# 8_IR.net
KiCad netlist of a schematic drawn in Altium Designer
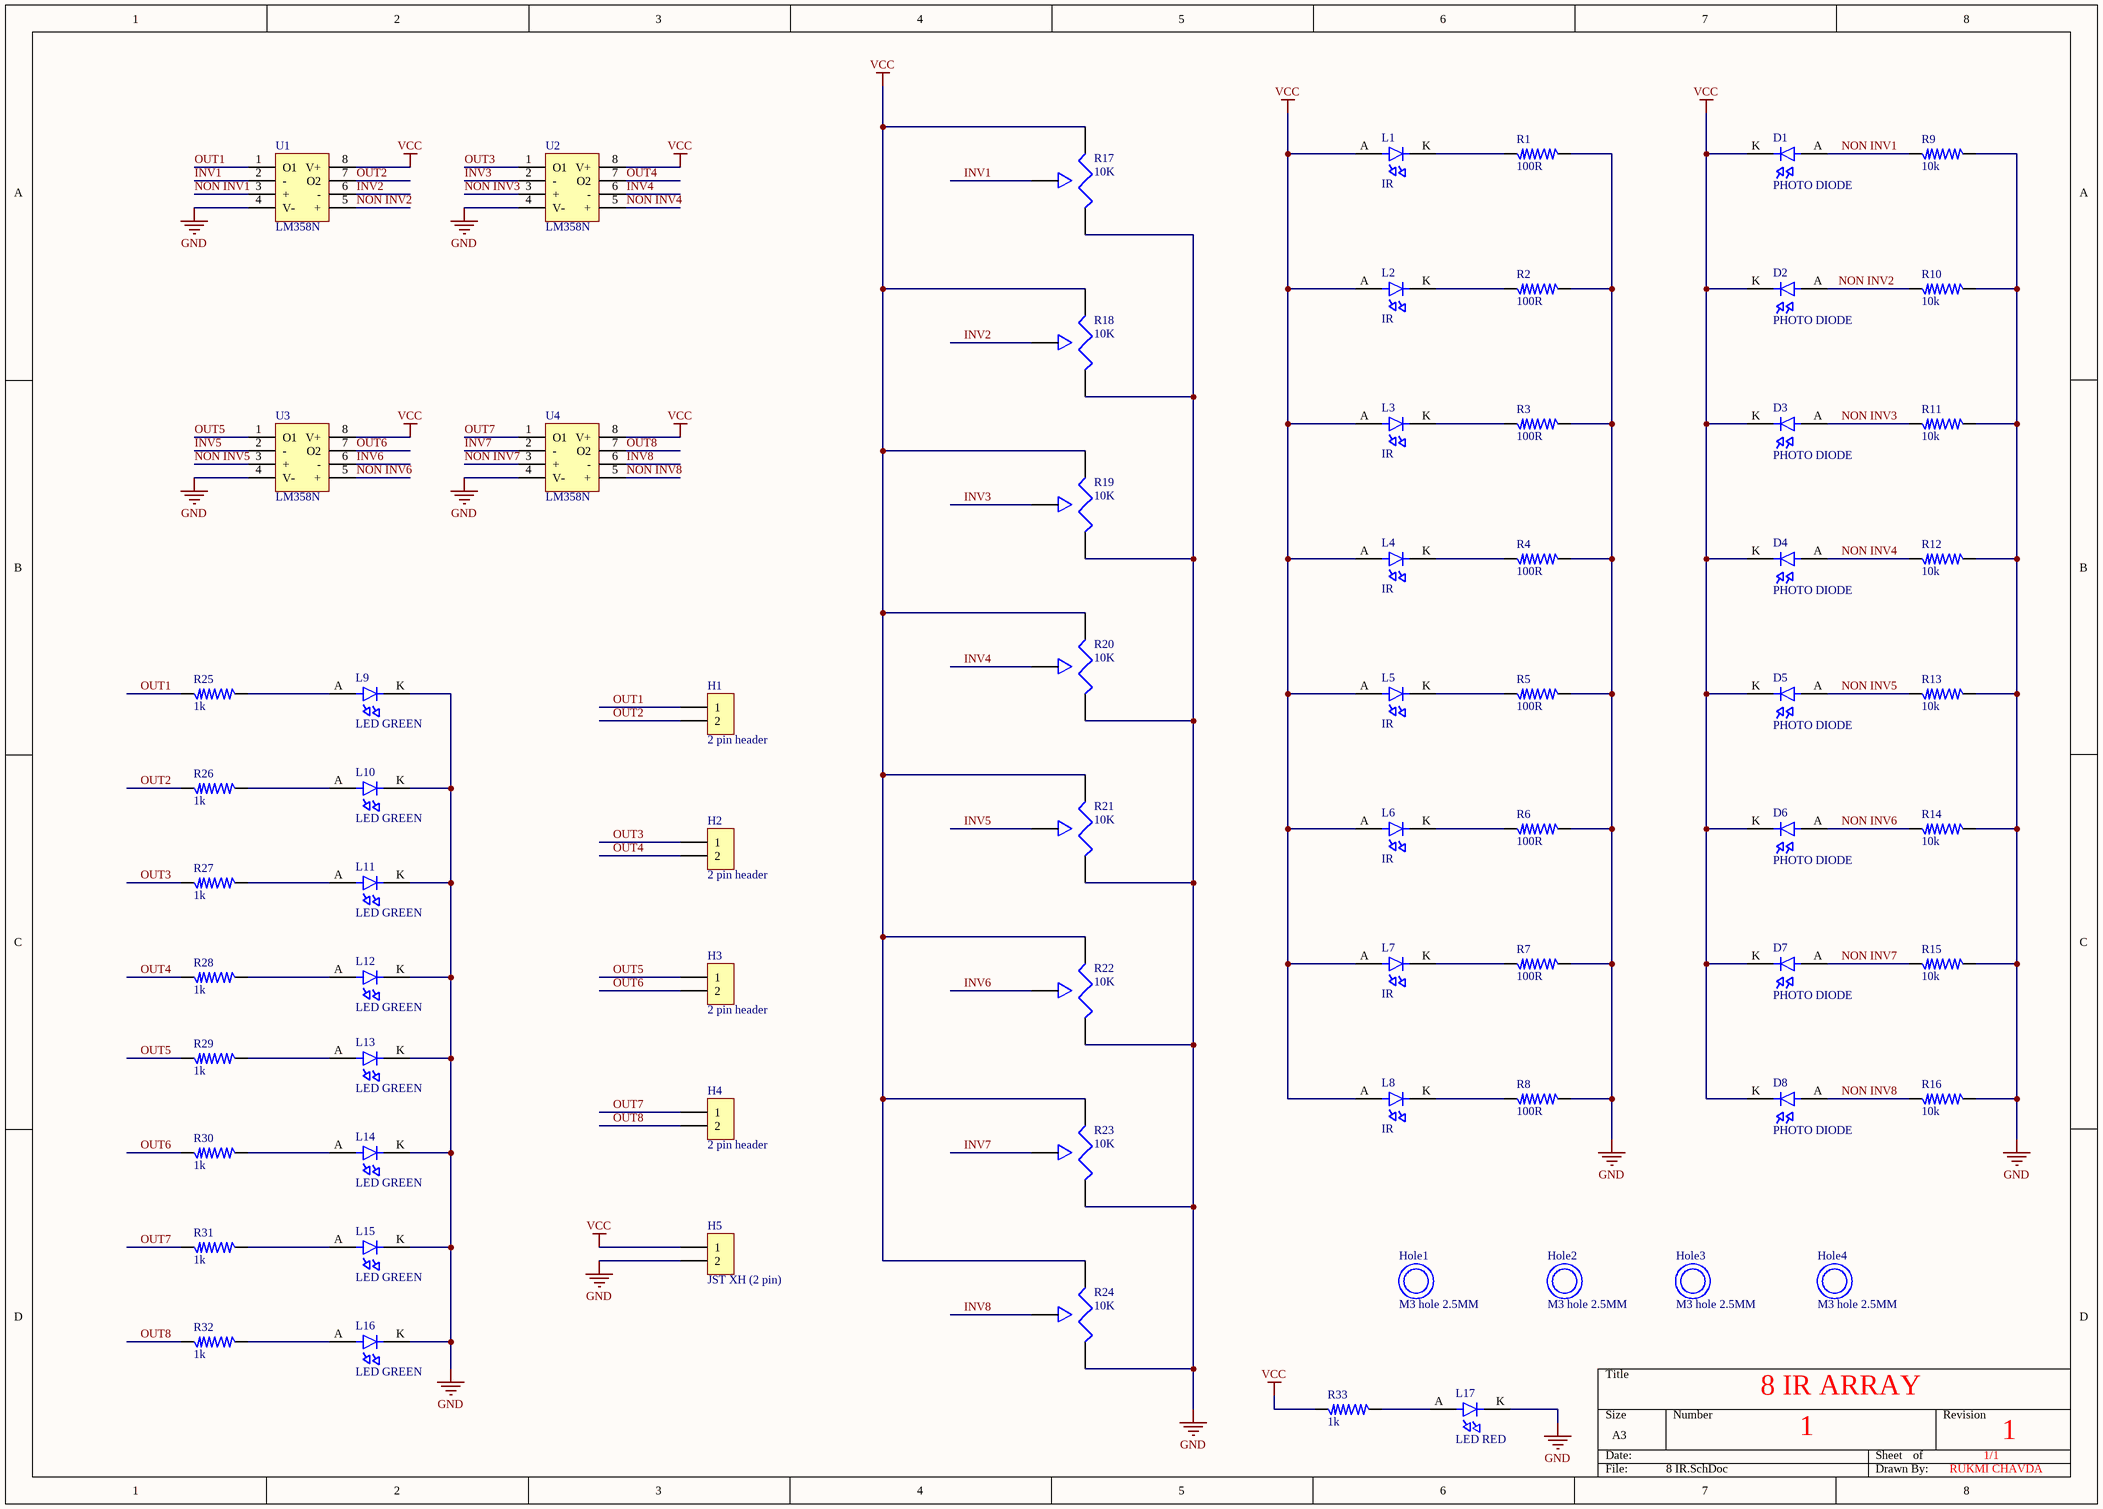
[diagram p0: 8 IR.SchDoc]

(export (version "E")
  (design (tool "Eeschema 10.0.6"))
  (components
    (comp (ref "D1")
      (value "PHOTO DIODE")
      (footprint "PHOYODIODE")
      (description "VISHAY         BPW24R             PHOTODIODE, 11PF")
      (libsource (lib "LEDs") (part "PHOTO DIODE"))
    )
    (comp (ref "D2")
      (value "PHOTO DIODE")
      (footprint "PHOYODIODE")
      (description "VISHAY         BPW24R             PHOTODIODE, 11PF")
      (libsource (lib "LEDs") (part "PHOTO DIODE"))
    )
    (comp (ref "D3")
      (value "PHOTO DIODE")
      (footprint "PHOYODIODE")
      (description "VISHAY         BPW24R             PHOTODIODE, 11PF")
      (libsource (lib "LEDs") (part "PHOTO DIODE"))
    )
    (comp (ref "D4")
      (value "PHOTO DIODE")
      (footprint "PHOYODIODE")
      (description "VISHAY         BPW24R             PHOTODIODE, 11PF")
      (libsource (lib "LEDs") (part "PHOTO DIODE"))
    )
    (comp (ref "D5")
      (value "PHOTO DIODE")
      (footprint "PHOYODIODE")
      (description "VISHAY         BPW24R             PHOTODIODE, 11PF")
      (libsource (lib "LEDs") (part "PHOTO DIODE"))
    )
    (comp (ref "D6")
      (value "PHOTO DIODE")
      (footprint "PHOYODIODE")
      (description "VISHAY         BPW24R             PHOTODIODE, 11PF")
      (libsource (lib "LEDs") (part "PHOTO DIODE"))
    )
    (comp (ref "D7")
      (value "PHOTO DIODE")
      (footprint "PHOYODIODE")
      (description "VISHAY         BPW24R             PHOTODIODE, 11PF")
      (libsource (lib "LEDs") (part "PHOTO DIODE"))
    )
    (comp (ref "D8")
      (value "PHOTO DIODE")
      (footprint "PHOYODIODE")
      (description "VISHAY         BPW24R             PHOTODIODE, 11PF")
      (libsource (lib "LEDs") (part "PHOTO DIODE"))
    )
    (comp (ref "H1")
      (value "2 pin header")
      (footprint "header 2")
      (description "connector")
      (libsource (lib "CONNECTORS AND HEADERS") (part "2 pin header"))
    )
    (comp (ref "H2")
      (value "2 pin header")
      (footprint "header 2")
      (description "connector")
      (libsource (lib "CONNECTORS AND HEADERS") (part "2 pin header"))
    )
    (comp (ref "H3")
      (value "2 pin header")
      (footprint "header 2")
      (description "connector")
      (libsource (lib "CONNECTORS AND HEADERS") (part "2 pin header"))
    )
    (comp (ref "H4")
      (value "2 pin header")
      (footprint "header 2")
      (description "connector")
      (libsource (lib "CONNECTORS AND HEADERS") (part "2 pin header"))
    )
    (comp (ref "H5")
      (value "JST XH (2 pin)")
      (footprint "jst 2 pin XH")
      (description "Conn Shrouded Header (4 Sides) HDR 2 POS 2.5mm Solder ST Thru-Hole Box")
      (fields
        (field (name "MANUFACTURER") "JST")
        (field (name "MANUFACTURER PART NUMBER") "B2B-XH-A(LF)(SN)")
      )
      (libsource (lib "CONNECTORS AND HEADERS") (part "JST XH (2 pin)"))
    )
    (comp (ref "Hole1")
      (value "M3 hole 2.5MM")
      (footprint "M3 Hole")
      (description "Mounting hole")
      (libsource (lib "Pades and Mounting holes") (part "M3 hole 2.5MM"))
    )
    (comp (ref "Hole2")
      (value "M3 hole 2.5MM")
      (footprint "M3 Hole")
      (description "Mounting hole")
      (libsource (lib "Pades and Mounting holes") (part "M3 hole 2.5MM"))
    )
    (comp (ref "Hole3")
      (value "M3 hole 2.5MM")
      (footprint "M3 Hole")
      (description "Mounting hole")
      (libsource (lib "Pades and Mounting holes") (part "M3 hole 2.5MM"))
    )
    (comp (ref "Hole4")
      (value "M3 hole 2.5MM")
      (footprint "M3 Hole")
      (description "Mounting hole")
      (libsource (lib "Pades and Mounting holes") (part "M3 hole 2.5MM"))
    )
    (comp (ref "L1")
      (value "IR")
      (footprint "LED IR")
      (description "EMITTER IR 940NM 100MA RADIAL")
      (libsource (lib "LEDs") (part "IR"))
    )
    (comp (ref "L2")
      (value "IR")
      (footprint "LED IR")
      (description "EMITTER IR 940NM 100MA RADIAL")
      (libsource (lib "LEDs") (part "IR"))
    )
    (comp (ref "L3")
      (value "IR")
      (footprint "LED IR")
      (description "EMITTER IR 940NM 100MA RADIAL")
      (libsource (lib "LEDs") (part "IR"))
    )
    (comp (ref "L4")
      (value "IR")
      (footprint "LED IR")
      (description "EMITTER IR 940NM 100MA RADIAL")
      (libsource (lib "LEDs") (part "IR"))
    )
    (comp (ref "L5")
      (value "IR")
      (footprint "LED IR")
      (description "EMITTER IR 940NM 100MA RADIAL")
      (libsource (lib "LEDs") (part "IR"))
    )
    (comp (ref "L6")
      (value "IR")
      (footprint "LED IR")
      (description "EMITTER IR 940NM 100MA RADIAL")
      (libsource (lib "LEDs") (part "IR"))
    )
    (comp (ref "L7")
      (value "IR")
      (footprint "LED IR")
      (description "EMITTER IR 940NM 100MA RADIAL")
      (libsource (lib "LEDs") (part "IR"))
    )
    (comp (ref "L8")
      (value "IR")
      (footprint "LED IR")
      (description "EMITTER IR 940NM 100MA RADIAL")
      (libsource (lib "LEDs") (part "IR"))
    )
    (comp (ref "L9")
      (value "LED GREEN")
      (footprint "LED GREEN")
      (description "LED GREEN DIFFUSED T-1 3/4 T/H")
      (libsource (lib "LEDs") (part "LED GREEN"))
    )
    (comp (ref "L10")
      (value "LED GREEN")
      (footprint "LED GREEN")
      (description "LED GREEN DIFFUSED T-1 3/4 T/H")
      (libsource (lib "LEDs") (part "LED GREEN"))
    )
    (comp (ref "L11")
      (value "LED GREEN")
      (footprint "LED GREEN")
      (description "LED GREEN DIFFUSED T-1 3/4 T/H")
      (libsource (lib "LEDs") (part "LED GREEN"))
    )
    (comp (ref "L12")
      (value "LED GREEN")
      (footprint "LED GREEN")
      (description "LED GREEN DIFFUSED T-1 3/4 T/H")
      (libsource (lib "LEDs") (part "LED GREEN"))
    )
    (comp (ref "L13")
      (value "LED GREEN")
      (footprint "LED GREEN")
      (description "LED GREEN DIFFUSED T-1 3/4 T/H")
      (libsource (lib "LEDs") (part "LED GREEN"))
    )
    (comp (ref "L14")
      (value "LED GREEN")
      (footprint "LED GREEN")
      (description "LED GREEN DIFFUSED T-1 3/4 T/H")
      (libsource (lib "LEDs") (part "LED GREEN"))
    )
    (comp (ref "L15")
      (value "LED GREEN")
      (footprint "LED GREEN")
      (description "LED GREEN DIFFUSED T-1 3/4 T/H")
      (libsource (lib "LEDs") (part "LED GREEN"))
    )
    (comp (ref "L16")
      (value "LED GREEN")
      (footprint "LED GREEN")
      (description "LED GREEN DIFFUSED T-1 3/4 T/H")
      (libsource (lib "LEDs") (part "LED GREEN"))
    )
    (comp (ref "L17")
      (value "LED RED")
      (footprint "LED RED")
      (description "LED RED CLEAR 5MM OVAL T/H")
      (libsource (lib "LEDs") (part "LED RED"))
    )
    (comp (ref "R1")
      (value "100R")
      (footprint "100R")
      (description "RES 100 OHM 1/4W 5% AXIAL")
      (fields (field (name "TOLERANCE") "5%"))
      (libsource (lib "Resistor") (part "100R"))
    )
    (comp (ref "R2")
      (value "100R")
      (footprint "100R")
      (description "RES 100 OHM 1/4W 5% AXIAL")
      (fields (field (name "TOLERANCE") "5%"))
      (libsource (lib "Resistor") (part "100R"))
    )
    (comp (ref "R3")
      (value "100R")
      (footprint "100R")
      (description "RES 100 OHM 1/4W 5% AXIAL")
      (fields (field (name "TOLERANCE") "5%"))
      (libsource (lib "Resistor") (part "100R"))
    )
    (comp (ref "R4")
      (value "100R")
      (footprint "100R")
      (description "RES 100 OHM 1/4W 5% AXIAL")
      (fields (field (name "TOLERANCE") "5%"))
      (libsource (lib "Resistor") (part "100R"))
    )
    (comp (ref "R5")
      (value "100R")
      (footprint "100R")
      (description "RES 100 OHM 1/4W 5% AXIAL")
      (fields (field (name "TOLERANCE") "5%"))
      (libsource (lib "Resistor") (part "100R"))
    )
    (comp (ref "R6")
      (value "100R")
      (footprint "100R")
      (description "RES 100 OHM 1/4W 5% AXIAL")
      (fields (field (name "TOLERANCE") "5%"))
      (libsource (lib "Resistor") (part "100R"))
    )
    (comp (ref "R7")
      (value "100R")
      (footprint "100R")
      (description "RES 100 OHM 1/4W 5% AXIAL")
      (fields (field (name "TOLERANCE") "5%"))
      (libsource (lib "Resistor") (part "100R"))
    )
    (comp (ref "R8")
      (value "100R")
      (footprint "100R")
      (description "RES 100 OHM 1/4W 5% AXIAL")
      (fields (field (name "TOLERANCE") "5%"))
      (libsource (lib "Resistor") (part "100R"))
    )
    (comp (ref "R9")
      (value "10k")
      (footprint "10k")
      (description "RES 10K OHM 1/4W 5% AXIAL")
      (fields (field (name "TOLERANCE") "5%"))
      (libsource (lib "Resistor") (part "10k"))
    )
    (comp (ref "R10")
      (value "10k")
      (footprint "10k")
      (description "RES 10K OHM 1/4W 5% AXIAL")
      (fields (field (name "TOLERANCE") "5%"))
      (libsource (lib "Resistor") (part "10k"))
    )
    (comp (ref "R11")
      (value "10k")
      (footprint "10k")
      (description "RES 10K OHM 1/4W 5% AXIAL")
      (fields (field (name "TOLERANCE") "5%"))
      (libsource (lib "Resistor") (part "10k"))
    )
    (comp (ref "R12")
      (value "10k")
      (footprint "10k")
      (description "RES 10K OHM 1/4W 5% AXIAL")
      (fields (field (name "TOLERANCE") "5%"))
      (libsource (lib "Resistor") (part "10k"))
    )
    (comp (ref "R13")
      (value "10k")
      (footprint "10k")
      (description "RES 10K OHM 1/4W 5% AXIAL")
      (fields (field (name "TOLERANCE") "5%"))
      (libsource (lib "Resistor") (part "10k"))
    )
    (comp (ref "R14")
      (value "10k")
      (footprint "10k")
      (description "RES 10K OHM 1/4W 5% AXIAL")
      (fields (field (name "TOLERANCE") "5%"))
      (libsource (lib "Resistor") (part "10k"))
    )
    (comp (ref "R15")
      (value "10k")
      (footprint "10k")
      (description "RES 10K OHM 1/4W 5% AXIAL")
      (fields (field (name "TOLERANCE") "5%"))
      (libsource (lib "Resistor") (part "10k"))
    )
    (comp (ref "R16")
      (value "10k")
      (footprint "10k")
      (description "RES 10K OHM 1/4W 5% AXIAL")
      (fields (field (name "TOLERANCE") "5%"))
      (libsource (lib "Resistor") (part "10k"))
    )
    (comp (ref "R17")
      (value "10K")
      (footprint "trimer pot")
      (description "Trimmer pot comman for all")
      (libsource (lib "Resistor") (part "potentiometer 1"))
    )
    (comp (ref "R18")
      (value "10K")
      (footprint "trimer pot")
      (description "Trimmer pot comman for all")
      (libsource (lib "Resistor") (part "potentiometer 1"))
    )
    (comp (ref "R19")
      (value "10K")
      (footprint "trimer pot")
      (description "Trimmer pot comman for all")
      (libsource (lib "Resistor") (part "potentiometer 1"))
    )
    (comp (ref "R20")
      (value "10K")
      (footprint "trimer pot")
      (description "Trimmer pot comman for all")
      (libsource (lib "Resistor") (part "potentiometer 1"))
    )
    (comp (ref "R21")
      (value "10K")
      (footprint "trimer pot")
      (description "Trimmer pot comman for all")
      (libsource (lib "Resistor") (part "potentiometer 1"))
    )
    (comp (ref "R22")
      (value "10K")
      (footprint "trimer pot")
      (description "Trimmer pot comman for all")
      (libsource (lib "Resistor") (part "potentiometer 1"))
    )
    (comp (ref "R23")
      (value "10K")
      (footprint "trimer pot")
      (description "Trimmer pot comman for all")
      (libsource (lib "Resistor") (part "potentiometer 1"))
    )
    (comp (ref "R24")
      (value "10K")
      (footprint "trimer pot")
      (description "Trimmer pot comman for all")
      (libsource (lib "Resistor") (part "potentiometer 1"))
    )
    (comp (ref "R25")
      (value "1k")
      (footprint "1k")
      (description "Res Carbon Film 1K Ohm 5% 0.25W(1/4W) -400ppm/? to 0ppm/? Conformal Coated AXL T/R")
      (fields (field (name "TOLERANCE") "5%"))
      (libsource (lib "Resistor") (part "1k"))
    )
    (comp (ref "R26")
      (value "1k")
      (footprint "1k")
      (description "Res Carbon Film 1K Ohm 5% 0.25W(1/4W) -400ppm/? to 0ppm/? Conformal Coated AXL T/R")
      (fields (field (name "TOLERANCE") "5%"))
      (libsource (lib "Resistor") (part "1k"))
    )
    (comp (ref "R27")
      (value "1k")
      (footprint "1k")
      (description "Res Carbon Film 1K Ohm 5% 0.25W(1/4W) -400ppm/? to 0ppm/? Conformal Coated AXL T/R")
      (fields (field (name "TOLERANCE") "5%"))
      (libsource (lib "Resistor") (part "1k"))
    )
    (comp (ref "R28")
      (value "1k")
      (footprint "1k")
      (description "Res Carbon Film 1K Ohm 5% 0.25W(1/4W) -400ppm/? to 0ppm/? Conformal Coated AXL T/R")
      (fields (field (name "TOLERANCE") "5%"))
      (libsource (lib "Resistor") (part "1k"))
    )
    (comp (ref "R29")
      (value "1k")
      (footprint "1k")
      (description "Res Carbon Film 1K Ohm 5% 0.25W(1/4W) -400ppm/? to 0ppm/? Conformal Coated AXL T/R")
      (fields (field (name "TOLERANCE") "5%"))
      (libsource (lib "Resistor") (part "1k"))
    )
    (comp (ref "R30")
      (value "1k")
      (footprint "1k")
      (description "Res Carbon Film 1K Ohm 5% 0.25W(1/4W) -400ppm/? to 0ppm/? Conformal Coated AXL T/R")
      (fields (field (name "TOLERANCE") "5%"))
      (libsource (lib "Resistor") (part "1k"))
    )
    (comp (ref "R31")
      (value "1k")
      (footprint "1k")
      (description "Res Carbon Film 1K Ohm 5% 0.25W(1/4W) -400ppm/? to 0ppm/? Conformal Coated AXL T/R")
      (fields (field (name "TOLERANCE") "5%"))
      (libsource (lib "Resistor") (part "1k"))
    )
    (comp (ref "R32")
      (value "1k")
      (footprint "1k")
      (description "Res Carbon Film 1K Ohm 5% 0.25W(1/4W) -400ppm/? to 0ppm/? Conformal Coated AXL T/R")
      (fields (field (name "TOLERANCE") "5%"))
      (libsource (lib "Resistor") (part "1k"))
    )
    (comp (ref "R33")
      (value "1k")
      (footprint "1k")
      (description "Res Carbon Film 1K Ohm 5% 0.25W(1/4W) -400ppm/? to 0ppm/? Conformal Coated AXL T/R")
      (fields (field (name "TOLERANCE") "5%"))
      (libsource (lib "Resistor") (part "1k"))
    )
    (comp (ref "U1")
      (value "LM358N")
      (footprint "LM 358 DIP")
      (description "TEXAS INSTRUMENTS - LM358N/NOPB - OP AMP DUAL")
      (libsource (lib "components") (part "LM358N"))
    )
    (comp (ref "U2")
      (value "LM358N")
      (footprint "LM 358 DIP")
      (description "TEXAS INSTRUMENTS - LM358N/NOPB - OP AMP DUAL")
      (libsource (lib "components") (part "LM358N"))
    )
    (comp (ref "U3")
      (value "LM358N")
      (footprint "LM 358 DIP")
      (description "TEXAS INSTRUMENTS - LM358N/NOPB - OP AMP DUAL")
      (libsource (lib "components") (part "LM358N"))
    )
    (comp (ref "U4")
      (value "LM358N")
      (footprint "LM 358 DIP")
      (description "TEXAS INSTRUMENTS - LM358N/NOPB - OP AMP DUAL")
      (libsource (lib "components") (part "LM358N"))
    )
  )
  (nets
    (net (code "1") (name "/INV1") (class "Default")
      (node (ref "R17") (pin "3") (pinfunction "3_3") (pintype "passive"))
      (node (ref "U1") (pin "2") (pinfunction "-_2") (pintype "passive"))
    )
    (net (code "2") (name "/INV2") (class "Default")
      (node (ref "R18") (pin "3") (pinfunction "3_3") (pintype "passive"))
      (node (ref "U1") (pin "6") (pinfunction "-_6") (pintype "passive"))
    )
    (net (code "3") (name "/INV3") (class "Default")
      (node (ref "R19") (pin "3") (pinfunction "3_3") (pintype "passive"))
      (node (ref "U2") (pin "2") (pinfunction "-_2") (pintype "passive"))
    )
    (net (code "4") (name "/INV4") (class "Default")
      (node (ref "R20") (pin "3") (pinfunction "3_3") (pintype "passive"))
      (node (ref "U2") (pin "6") (pinfunction "-_6") (pintype "passive"))
    )
    (net (code "5") (name "/INV5") (class "Default")
      (node (ref "R21") (pin "3") (pinfunction "3_3") (pintype "passive"))
      (node (ref "U3") (pin "2") (pinfunction "-_2") (pintype "passive"))
    )
    (net (code "6") (name "/INV6") (class "Default")
      (node (ref "R22") (pin "3") (pinfunction "3_3") (pintype "passive"))
      (node (ref "U3") (pin "6") (pinfunction "-_6") (pintype "passive"))
    )
    (net (code "7") (name "/INV7") (class "Default")
      (node (ref "R23") (pin "3") (pinfunction "3_3") (pintype "passive"))
      (node (ref "U4") (pin "2") (pinfunction "-_2") (pintype "passive"))
    )
    (net (code "8") (name "/INV8") (class "Default")
      (node (ref "R24") (pin "3") (pinfunction "3_3") (pintype "passive"))
      (node (ref "U4") (pin "6") (pinfunction "-_6") (pintype "passive"))
    )
    (net (code "9") (name "/NON INV1") (class "Default")
      (node (ref "D1") (pin "A") (pintype "passive"))
      (node (ref "R9") (pin "1") (pinfunction "1_1") (pintype "passive"))
      (node (ref "U1") (pin "3") (pinfunction "+_3") (pintype "passive"))
    )
    (net (code "10") (name "/NON INV2") (class "Default")
      (node (ref "D2") (pin "A") (pintype "passive"))
      (node (ref "R10") (pin "1") (pinfunction "1_1") (pintype "passive"))
      (node (ref "U1") (pin "5") (pinfunction "+_5") (pintype "passive"))
    )
    (net (code "11") (name "/NON INV3") (class "Default")
      (node (ref "D3") (pin "A") (pintype "passive"))
      (node (ref "R11") (pin "1") (pinfunction "1_1") (pintype "passive"))
      (node (ref "U2") (pin "3") (pinfunction "+_3") (pintype "passive"))
    )
    (net (code "12") (name "/NON INV4") (class "Default")
      (node (ref "D4") (pin "A") (pintype "passive"))
      (node (ref "R12") (pin "1") (pinfunction "1_1") (pintype "passive"))
      (node (ref "U2") (pin "5") (pinfunction "+_5") (pintype "passive"))
    )
    (net (code "13") (name "/NON INV5") (class "Default")
      (node (ref "D5") (pin "A") (pintype "passive"))
      (node (ref "R13") (pin "1") (pinfunction "1_1") (pintype "passive"))
      (node (ref "U3") (pin "3") (pinfunction "+_3") (pintype "passive"))
    )
    (net (code "14") (name "/NON INV6") (class "Default")
      (node (ref "D6") (pin "A") (pintype "passive"))
      (node (ref "R14") (pin "1") (pinfunction "1_1") (pintype "passive"))
      (node (ref "U3") (pin "5") (pinfunction "+_5") (pintype "passive"))
    )
    (net (code "15") (name "/NON INV7") (class "Default")
      (node (ref "D7") (pin "A") (pintype "passive"))
      (node (ref "R15") (pin "1") (pinfunction "1_1") (pintype "passive"))
      (node (ref "U4") (pin "3") (pinfunction "+_3") (pintype "passive"))
    )
    (net (code "16") (name "/NON INV8") (class "Default")
      (node (ref "D8") (pin "A") (pintype "passive"))
      (node (ref "R16") (pin "1") (pinfunction "1_1") (pintype "passive"))
      (node (ref "U4") (pin "5") (pinfunction "+_5") (pintype "passive"))
    )
    (net (code "17") (name "/OUT1") (class "Default")
      (node (ref "H1") (pin "1") (pinfunction "1_1") (pintype "passive"))
      (node (ref "R25") (pin "1") (pinfunction "1_1") (pintype "passive"))
      (node (ref "U1") (pin "1") (pinfunction "O1_1") (pintype "passive"))
    )
    (net (code "18") (name "/OUT2") (class "Default")
      (node (ref "H1") (pin "2") (pinfunction "2_2") (pintype "passive"))
      (node (ref "R26") (pin "1") (pinfunction "1_1") (pintype "passive"))
      (node (ref "U1") (pin "7") (pinfunction "O2_7") (pintype "passive"))
    )
    (net (code "19") (name "/OUT3") (class "Default")
      (node (ref "H2") (pin "1") (pinfunction "1_1") (pintype "passive"))
      (node (ref "R27") (pin "1") (pinfunction "1_1") (pintype "passive"))
      (node (ref "U2") (pin "1") (pinfunction "O1_1") (pintype "passive"))
    )
    (net (code "20") (name "/OUT4") (class "Default")
      (node (ref "H2") (pin "2") (pinfunction "2_2") (pintype "passive"))
      (node (ref "R28") (pin "1") (pinfunction "1_1") (pintype "passive"))
      (node (ref "U2") (pin "7") (pinfunction "O2_7") (pintype "passive"))
    )
    (net (code "21") (name "/OUT5") (class "Default")
      (node (ref "H3") (pin "1") (pinfunction "1_1") (pintype "passive"))
      (node (ref "R29") (pin "1") (pinfunction "1_1") (pintype "passive"))
      (node (ref "U3") (pin "1") (pinfunction "O1_1") (pintype "passive"))
    )
    (net (code "22") (name "/OUT6") (class "Default")
      (node (ref "H3") (pin "2") (pinfunction "2_2") (pintype "passive"))
      (node (ref "R30") (pin "1") (pinfunction "1_1") (pintype "passive"))
      (node (ref "U3") (pin "7") (pinfunction "O2_7") (pintype "passive"))
    )
    (net (code "23") (name "/OUT7") (class "Default")
      (node (ref "H4") (pin "1") (pinfunction "1_1") (pintype "passive"))
      (node (ref "R31") (pin "1") (pinfunction "1_1") (pintype "passive"))
      (node (ref "U4") (pin "1") (pinfunction "O1_1") (pintype "passive"))
    )
    (net (code "24") (name "/OUT8") (class "Default")
      (node (ref "H4") (pin "2") (pinfunction "2_2") (pintype "passive"))
      (node (ref "R32") (pin "1") (pinfunction "1_1") (pintype "passive"))
      (node (ref "U4") (pin "7") (pinfunction "O2_7") (pintype "passive"))
    )
    (net (code "25") (name "GND") (class "Default")
      (node (ref "H5") (pin "2") (pinfunction "2_2") (pintype "passive"))
      (node (ref "L10") (pin "K") (pintype "passive"))
      (node (ref "L11") (pin "K") (pintype "passive"))
      (node (ref "L12") (pin "K") (pintype "passive"))
      (node (ref "L13") (pin "K") (pintype "passive"))
      (node (ref "L14") (pin "K") (pintype "passive"))
      (node (ref "L15") (pin "K") (pintype "passive"))
      (node (ref "L16") (pin "K") (pintype "passive"))
      (node (ref "L17") (pin "K") (pintype "passive"))
      (node (ref "L9") (pin "K") (pintype "passive"))
      (node (ref "R1") (pin "2") (pinfunction "2_2") (pintype "passive"))
      (node (ref "R10") (pin "2") (pinfunction "2_2") (pintype "passive"))
      (node (ref "R11") (pin "2") (pinfunction "2_2") (pintype "passive"))
      (node (ref "R12") (pin "2") (pinfunction "2_2") (pintype "passive"))
      (node (ref "R13") (pin "2") (pinfunction "2_2") (pintype "passive"))
      (node (ref "R14") (pin "2") (pinfunction "2_2") (pintype "passive"))
      (node (ref "R15") (pin "2") (pinfunction "2_2") (pintype "passive"))
      (node (ref "R16") (pin "2") (pinfunction "2_2") (pintype "passive"))
      (node (ref "R17") (pin "1") (pinfunction "1_1") (pintype "passive"))
      (node (ref "R18") (pin "1") (pinfunction "1_1") (pintype "passive"))
      (node (ref "R19") (pin "1") (pinfunction "1_1") (pintype "passive"))
      (node (ref "R2") (pin "2") (pinfunction "2_2") (pintype "passive"))
      (node (ref "R20") (pin "1") (pinfunction "1_1") (pintype "passive"))
      (node (ref "R21") (pin "1") (pinfunction "1_1") (pintype "passive"))
      (node (ref "R22") (pin "1") (pinfunction "1_1") (pintype "passive"))
      (node (ref "R23") (pin "1") (pinfunction "1_1") (pintype "passive"))
      (node (ref "R24") (pin "1") (pinfunction "1_1") (pintype "passive"))
      (node (ref "R3") (pin "2") (pinfunction "2_2") (pintype "passive"))
      (node (ref "R4") (pin "2") (pinfunction "2_2") (pintype "passive"))
      (node (ref "R5") (pin "2") (pinfunction "2_2") (pintype "passive"))
      (node (ref "R6") (pin "2") (pinfunction "2_2") (pintype "passive"))
      (node (ref "R7") (pin "2") (pinfunction "2_2") (pintype "passive"))
      (node (ref "R8") (pin "2") (pinfunction "2_2") (pintype "passive"))
      (node (ref "R9") (pin "2") (pinfunction "2_2") (pintype "passive"))
      (node (ref "U1") (pin "4") (pinfunction "V-_4") (pintype "passive"))
      (node (ref "U2") (pin "4") (pinfunction "V-_4") (pintype "passive"))
      (node (ref "U3") (pin "4") (pinfunction "V-_4") (pintype "passive"))
      (node (ref "U4") (pin "4") (pinfunction "V-_4") (pintype "passive"))
    )
    (net (code "26") (name "Net-(L1-PadK)") (class "Default")
      (node (ref "L1") (pin "K") (pintype "passive"))
      (node (ref "R1") (pin "1") (pinfunction "1_1") (pintype "passive"))
    )
    (net (code "27") (name "Net-(L2-PadK)") (class "Default")
      (node (ref "L2") (pin "K") (pintype "passive"))
      (node (ref "R2") (pin "1") (pinfunction "1_1") (pintype "passive"))
    )
    (net (code "28") (name "Net-(L3-PadK)") (class "Default")
      (node (ref "L3") (pin "K") (pintype "passive"))
      (node (ref "R3") (pin "1") (pinfunction "1_1") (pintype "passive"))
    )
    (net (code "29") (name "Net-(L4-PadK)") (class "Default")
      (node (ref "L4") (pin "K") (pintype "passive"))
      (node (ref "R4") (pin "1") (pinfunction "1_1") (pintype "passive"))
    )
    (net (code "30") (name "Net-(L5-PadK)") (class "Default")
      (node (ref "L5") (pin "K") (pintype "passive"))
      (node (ref "R5") (pin "1") (pinfunction "1_1") (pintype "passive"))
    )
    (net (code "31") (name "Net-(L6-PadK)") (class "Default")
      (node (ref "L6") (pin "K") (pintype "passive"))
      (node (ref "R6") (pin "1") (pinfunction "1_1") (pintype "passive"))
    )
    (net (code "32") (name "Net-(L7-PadK)") (class "Default")
      (node (ref "L7") (pin "K") (pintype "passive"))
      (node (ref "R7") (pin "1") (pinfunction "1_1") (pintype "passive"))
    )
    (net (code "33") (name "Net-(L8-PadK)") (class "Default")
      (node (ref "L8") (pin "K") (pintype "passive"))
      (node (ref "R8") (pin "1") (pinfunction "1_1") (pintype "passive"))
    )
    (net (code "34") (name "Net-(L9-PadA)") (class "Default")
      (node (ref "L9") (pin "A") (pintype "passive"))
      (node (ref "R25") (pin "2") (pinfunction "2_2") (pintype "passive"))
    )
    (net (code "35") (name "Net-(L10-PadA)") (class "Default")
      (node (ref "L10") (pin "A") (pintype "passive"))
      (node (ref "R26") (pin "2") (pinfunction "2_2") (pintype "passive"))
    )
    (net (code "36") (name "Net-(L11-PadA)") (class "Default")
      (node (ref "L11") (pin "A") (pintype "passive"))
      (node (ref "R27") (pin "2") (pinfunction "2_2") (pintype "passive"))
    )
    (net (code "37") (name "Net-(L12-PadA)") (class "Default")
      (node (ref "L12") (pin "A") (pintype "passive"))
      (node (ref "R28") (pin "2") (pinfunction "2_2") (pintype "passive"))
    )
    (net (code "38") (name "Net-(L13-PadA)") (class "Default")
      (node (ref "L13") (pin "A") (pintype "passive"))
      (node (ref "R29") (pin "2") (pinfunction "2_2") (pintype "passive"))
    )
    (net (code "39") (name "Net-(L14-PadA)") (class "Default")
      (node (ref "L14") (pin "A") (pintype "passive"))
      (node (ref "R30") (pin "2") (pinfunction "2_2") (pintype "passive"))
    )
    (net (code "40") (name "Net-(L15-PadA)") (class "Default")
      (node (ref "L15") (pin "A") (pintype "passive"))
      (node (ref "R31") (pin "2") (pinfunction "2_2") (pintype "passive"))
    )
    (net (code "41") (name "Net-(L16-PadA)") (class "Default")
      (node (ref "L16") (pin "A") (pintype "passive"))
      (node (ref "R32") (pin "2") (pinfunction "2_2") (pintype "passive"))
    )
    (net (code "42") (name "Net-(L17-PadA)") (class "Default")
      (node (ref "L17") (pin "A") (pintype "passive"))
      (node (ref "R33") (pin "2") (pinfunction "2_2") (pintype "passive"))
    )
    (net (code "43") (name "VCC") (class "Default")
      (node (ref "D1") (pin "K") (pintype "passive"))
      (node (ref "D2") (pin "K") (pintype "passive"))
      (node (ref "D3") (pin "K") (pintype "passive"))
      (node (ref "D4") (pin "K") (pintype "passive"))
      (node (ref "D5") (pin "K") (pintype "passive"))
      (node (ref "D6") (pin "K") (pintype "passive"))
      (node (ref "D7") (pin "K") (pintype "passive"))
      (node (ref "D8") (pin "K") (pintype "passive"))
      (node (ref "H5") (pin "1") (pinfunction "1_1") (pintype "passive"))
      (node (ref "L1") (pin "A") (pintype "passive"))
      (node (ref "L2") (pin "A") (pintype "passive"))
      (node (ref "L3") (pin "A") (pintype "passive"))
      (node (ref "L4") (pin "A") (pintype "passive"))
      (node (ref "L5") (pin "A") (pintype "passive"))
      (node (ref "L6") (pin "A") (pintype "passive"))
      (node (ref "L7") (pin "A") (pintype "passive"))
      (node (ref "L8") (pin "A") (pintype "passive"))
      (node (ref "R17") (pin "2") (pinfunction "2_2") (pintype "passive"))
      (node (ref "R18") (pin "2") (pinfunction "2_2") (pintype "passive"))
      (node (ref "R19") (pin "2") (pinfunction "2_2") (pintype "passive"))
      (node (ref "R20") (pin "2") (pinfunction "2_2") (pintype "passive"))
      (node (ref "R21") (pin "2") (pinfunction "2_2") (pintype "passive"))
      (node (ref "R22") (pin "2") (pinfunction "2_2") (pintype "passive"))
      (node (ref "R23") (pin "2") (pinfunction "2_2") (pintype "passive"))
      (node (ref "R24") (pin "2") (pinfunction "2_2") (pintype "passive"))
      (node (ref "R33") (pin "1") (pinfunction "1_1") (pintype "passive"))
      (node (ref "U1") (pin "8") (pinfunction "V+_8") (pintype "passive"))
      (node (ref "U2") (pin "8") (pinfunction "V+_8") (pintype "passive"))
      (node (ref "U3") (pin "8") (pinfunction "V+_8") (pintype "passive"))
      (node (ref "U4") (pin "8") (pinfunction "V+_8") (pintype "passive"))
    )
  )
)
